# sequential_switch_rev_0_8.net
KiCad netlist of a schematic drawn in EAGLE
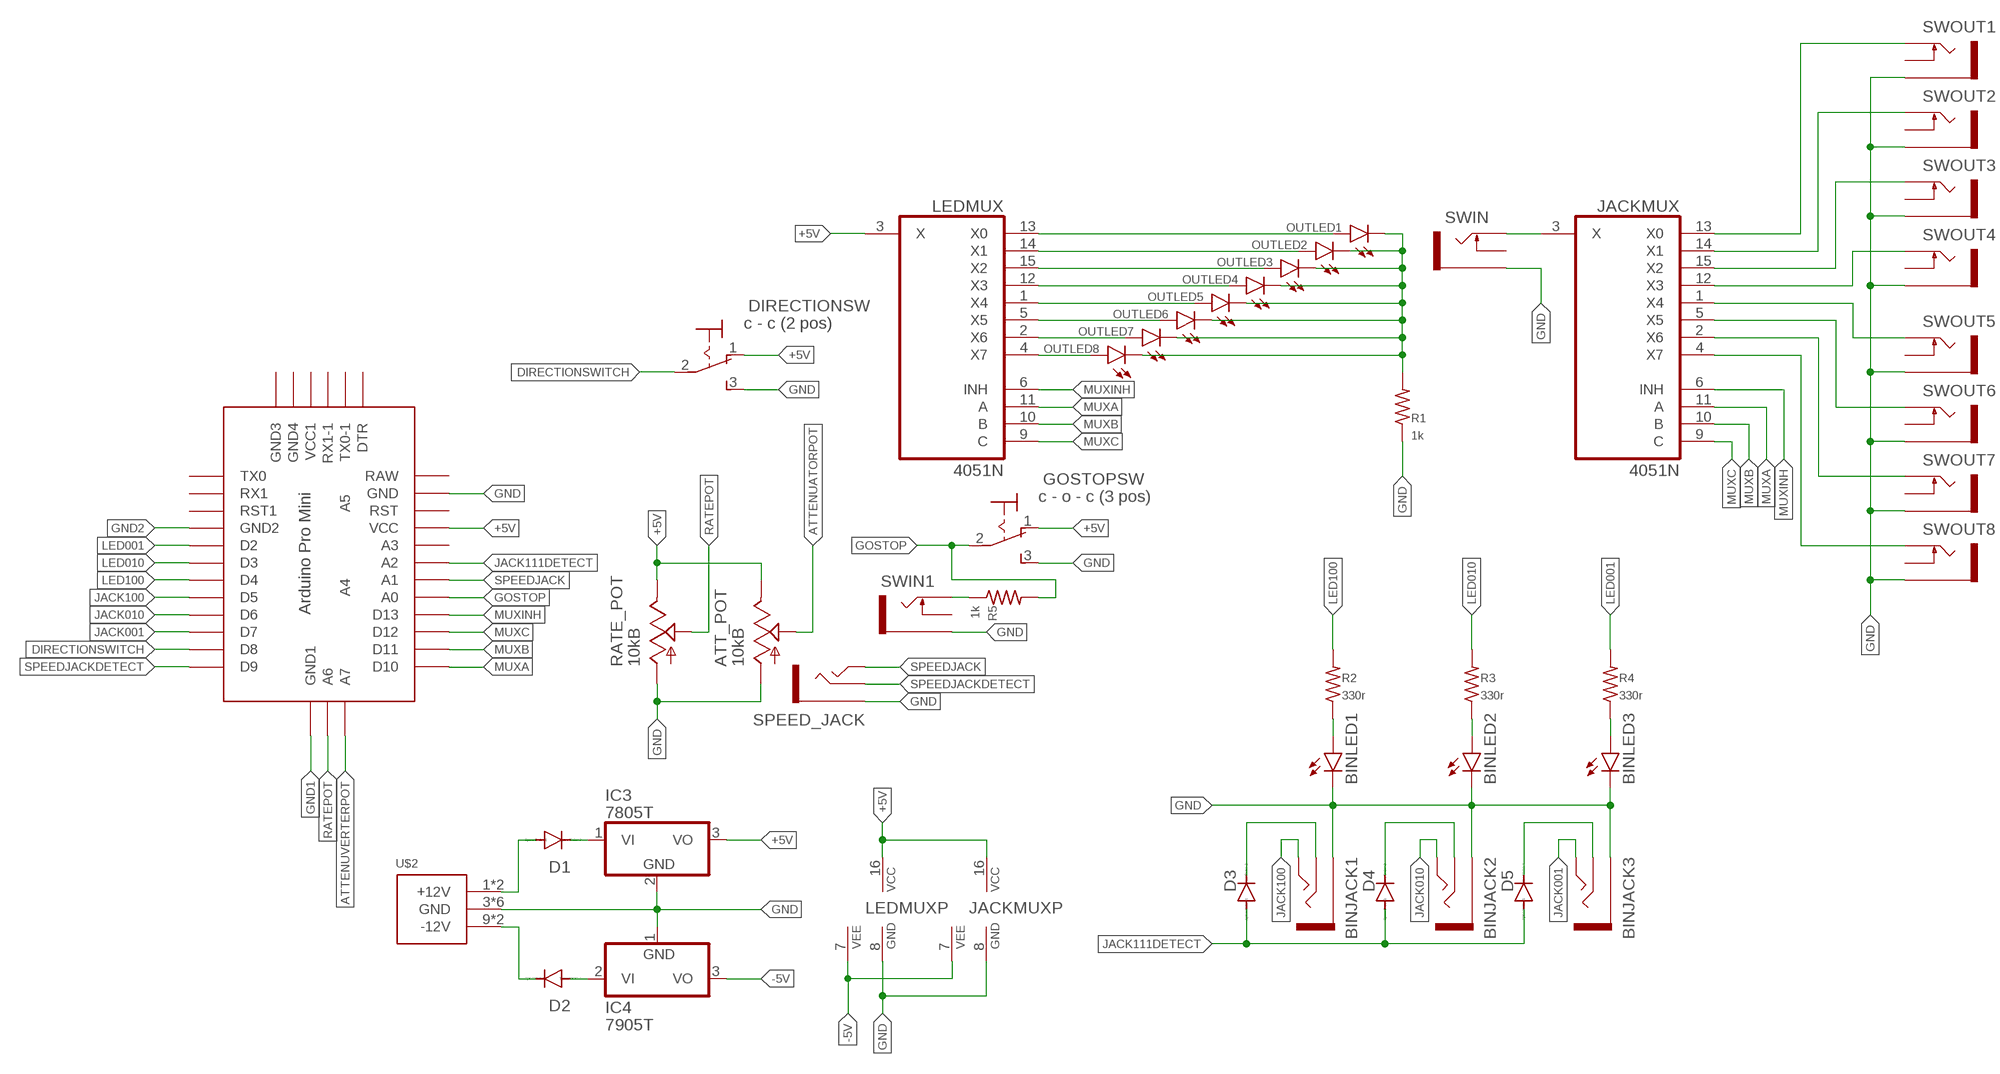
[diagram p0: schematic, sheet 1]

(export (version "E")
  (design (tool "Eeschema 10.0.6"))
  (components
    (comp (ref "ATT_POT")
      (value "10kB")
      (footprint "eagle-import:ALPS_POT_VERTICAL_PS")
      (libsource (lib "eagle-import") (part "POT_USVERTICAL_PS"))
    )
    (comp (ref "BINJACK1")
      (value "JACK-STEREO")
      (footprint "eagle-import:WQP-PJ301M-12_JACK")
      (libsource (lib "eagle-import") (part "JACK-STEREO"))
    )
    (comp (ref "BINJACK2")
      (value "JACK-STEREO")
      (footprint "eagle-import:WQP-PJ301M-12_JACK")
      (libsource (lib "eagle-import") (part "JACK-STEREO"))
    )
    (comp (ref "BINJACK3")
      (value "JACK-STEREO")
      (footprint "eagle-import:WQP-PJ301M-12_JACK")
      (libsource (lib "eagle-import") (part "JACK-STEREO"))
    )
    (comp (ref "BINLED1")
      (value "LED5MM")
      (footprint "eagle-import:LED5MM")
      (libsource (lib "eagle-import") (part "LED5MM"))
    )
    (comp (ref "BINLED2")
      (value "LED5MM")
      (footprint "eagle-import:LED5MM")
      (libsource (lib "eagle-import") (part "LED5MM"))
    )
    (comp (ref "BINLED3")
      (value "LED5MM")
      (footprint "eagle-import:LED5MM")
      (libsource (lib "eagle-import") (part "LED5MM"))
    )
    (comp (ref "D1")
      (value "1N4004")
      (footprint "eagle-import:DO41-10")
      (libsource (lib "eagle-import") (part "1N4004"))
    )
    (comp (ref "D2")
      (value "1N4004")
      (footprint "eagle-import:DO41-10")
      (libsource (lib "eagle-import") (part "1N4004"))
    )
    (comp (ref "D3")
      (value "1N4446")
      (footprint "eagle-import:DO35-10")
      (libsource (lib "eagle-import") (part "1N4446"))
    )
    (comp (ref "D4")
      (value "1N4446")
      (footprint "eagle-import:DO35-10")
      (libsource (lib "eagle-import") (part "1N4446"))
    )
    (comp (ref "D5")
      (value "1N4446")
      (footprint "eagle-import:DO35-10")
      (libsource (lib "eagle-import") (part "1N4446"))
    )
    (comp (ref "DIRECTIONSW")
      (value "c - c (2 pos)")
      (footprint "eagle-import:320-916")
      (libsource (lib "eagle-import") (part "320-916"))
    )
    (comp (ref "GOSTOPSW")
      (value "c - o - c (3 pos)")
      (footprint "eagle-import:320-916")
      (libsource (lib "eagle-import") (part "320-916"))
    )
    (comp (ref "IC3")
      (value "7805T")
      (footprint "eagle-import:TO220H")
      (libsource (lib "eagle-import") (part "78T05"))
    )
    (comp (ref "IC4")
      (value "7905T")
      (footprint "eagle-import:TO220H")
      (libsource (lib "eagle-import") (part "79T05"))
    )
    (comp (ref "JACKMUX")
      (value "4051N")
      (footprint "eagle-import:DIL16")
      (libsource (lib "eagle-import") (part "4051N"))
    )
    (comp (ref "LEDMUX")
      (value "4051N")
      (footprint "eagle-import:DIL16")
      (libsource (lib "eagle-import") (part "4051N"))
    )
    (comp (ref "OUTLED1")
      (value "LED3MM")
      (footprint "eagle-import:LED3MM")
      (libsource (lib "eagle-import") (part "LED3MM"))
    )
    (comp (ref "OUTLED2")
      (value "LED3MM")
      (footprint "eagle-import:LED3MM")
      (libsource (lib "eagle-import") (part "LED3MM"))
    )
    (comp (ref "OUTLED3")
      (value "LED3MM")
      (footprint "eagle-import:LED3MM")
      (libsource (lib "eagle-import") (part "LED3MM"))
    )
    (comp (ref "OUTLED4")
      (value "LED3MM")
      (footprint "eagle-import:LED3MM")
      (libsource (lib "eagle-import") (part "LED3MM"))
    )
    (comp (ref "OUTLED5")
      (value "LED3MM")
      (footprint "eagle-import:LED3MM")
      (libsource (lib "eagle-import") (part "LED3MM"))
    )
    (comp (ref "OUTLED6")
      (value "LED3MM")
      (footprint "eagle-import:LED3MM")
      (libsource (lib "eagle-import") (part "LED3MM"))
    )
    (comp (ref "OUTLED7")
      (value "LED3MM")
      (footprint "eagle-import:LED3MM")
      (libsource (lib "eagle-import") (part "LED3MM"))
    )
    (comp (ref "OUTLED8")
      (value "LED3MM")
      (footprint "eagle-import:LED3MM")
      (libsource (lib "eagle-import") (part "LED3MM"))
    )
    (comp (ref "R1")
      (value "1k")
      (footprint "eagle-import:0204_7")
      (libsource (lib "eagle-import") (part "R-US_0204/7"))
    )
    (comp (ref "R2")
      (value "330r")
      (footprint "eagle-import:0204_7")
      (libsource (lib "eagle-import") (part "R-US_0204/7"))
    )
    (comp (ref "R3")
      (value "330r")
      (footprint "eagle-import:0204_7")
      (libsource (lib "eagle-import") (part "R-US_0204/7"))
    )
    (comp (ref "R4")
      (value "330r")
      (footprint "eagle-import:0204_7")
      (libsource (lib "eagle-import") (part "R-US_0204/7"))
    )
    (comp (ref "R5")
      (value "1k")
      (footprint "eagle-import:0204_7")
      (libsource (lib "eagle-import") (part "R-US_0204/7"))
    )
    (comp (ref "RATE_POT")
      (value "10kB")
      (footprint "eagle-import:ALPS_POT_VERTICAL_PS")
      (libsource (lib "eagle-import") (part "POT_USVERTICAL_PS"))
    )
    (comp (ref "SPEED_JACK")
      (value "JACK-STEREO")
      (footprint "eagle-import:WQP-PJ301M-12_JACK")
      (libsource (lib "eagle-import") (part "JACK-STEREO"))
    )
    (comp (ref "SWIN")
      (value "WQP-PJ301M-12_JACK")
      (footprint "eagle-import:WQP-PJ301M-12_JACK")
      (libsource (lib "eagle-import") (part "WQP-PJ301M-12_JACK"))
    )
    (comp (ref "SWIN1")
      (value "WQP-PJ301M-12_JACK")
      (footprint "eagle-import:WQP-PJ301M-12_JACK")
      (libsource (lib "eagle-import") (part "WQP-PJ301M-12_JACK"))
    )
    (comp (ref "SWOUT1")
      (value "WQP-PJ301M-12_JACK")
      (footprint "eagle-import:WQP-PJ301M-12_JACK")
      (libsource (lib "eagle-import") (part "WQP-PJ301M-12_JACK"))
    )
    (comp (ref "SWOUT2")
      (value "WQP-PJ301M-12_JACK")
      (footprint "eagle-import:WQP-PJ301M-12_JACK")
      (libsource (lib "eagle-import") (part "WQP-PJ301M-12_JACK"))
    )
    (comp (ref "SWOUT3")
      (value "WQP-PJ301M-12_JACK")
      (footprint "eagle-import:WQP-PJ301M-12_JACK")
      (libsource (lib "eagle-import") (part "WQP-PJ301M-12_JACK"))
    )
    (comp (ref "SWOUT4")
      (value "WQP-PJ301M-12_JACK")
      (footprint "eagle-import:WQP-PJ301M-12_JACK")
      (libsource (lib "eagle-import") (part "WQP-PJ301M-12_JACK"))
    )
    (comp (ref "SWOUT5")
      (value "WQP-PJ301M-12_JACK")
      (footprint "eagle-import:WQP-PJ301M-12_JACK")
      (libsource (lib "eagle-import") (part "WQP-PJ301M-12_JACK"))
    )
    (comp (ref "SWOUT6")
      (value "WQP-PJ301M-12_JACK")
      (footprint "eagle-import:WQP-PJ301M-12_JACK")
      (libsource (lib "eagle-import") (part "WQP-PJ301M-12_JACK"))
    )
    (comp (ref "SWOUT7")
      (value "WQP-PJ301M-12_JACK")
      (footprint "eagle-import:WQP-PJ301M-12_JACK")
      (libsource (lib "eagle-import") (part "WQP-PJ301M-12_JACK"))
    )
    (comp (ref "SWOUT8")
      (value "WQP-PJ301M-12_JACK")
      (footprint "eagle-import:WQP-PJ301M-12_JACK")
      (libsource (lib "eagle-import") (part "WQP-PJ301M-12_JACK"))
    )
    (comp (ref "U$1")
      (value "ABK-PRO-MINI")
      (footprint "eagle-import:ABK-PRO-MINI")
      (libsource (lib "eagle-import") (part "ABK-PRO-MINI"))
    )
    (comp (ref "U$2")
      (value "POWER_SIMPLE")
      (footprint "eagle-import:POWER_10_NSTRIPE")
      (libsource (lib "eagle-import") (part "POWER_SIMPLE"))
    )
  )
  (nets
    (net (code "1") (name "+5V") (class "Default")
      (node (ref "ATT_POT") (pin "P$1") (pinfunction "E_P$1") (pintype "passive"))
      (node (ref "DIRECTIONSW") (pin "1") (pinfunction "O_1") (pintype "passive"))
      (node (ref "GOSTOPSW") (pin "1") (pinfunction "O_1") (pintype "passive"))
      (node (ref "IC3") (pin "3") (pinfunction "VO_3") (pintype "passive"))
      (node (ref "JACKMUX") (pin "16") (pinfunction "VCC_16") (pintype "power_in"))
      (node (ref "LEDMUX") (pin "16") (pinfunction "VCC_16") (pintype "power_in"))
      (node (ref "LEDMUX") (pin "3") (pinfunction "X_3") (pintype "bidirectional"))
      (node (ref "RATE_POT") (pin "P$1") (pinfunction "E_P$1") (pintype "passive"))
      (node (ref "U$1") (pin "VCC") (pinfunction "VCC_VCC") (pintype "bidirectional"))
    )
    (net (code "2") (name "-5V") (class "Default")
      (node (ref "IC4") (pin "3") (pinfunction "VO_3") (pintype "passive"))
      (node (ref "JACKMUX") (pin "7") (pinfunction "VEE_7") (pintype "power_in"))
      (node (ref "LEDMUX") (pin "7") (pinfunction "VEE_7") (pintype "power_in"))
    )
    (net (code "3") (name "ATTENUATORPOT") (class "Default")
      (node (ref "ATT_POT") (pin "P$2") (pinfunction "S_P$2") (pintype "passive"))
    )
    (net (code "4") (name "ATTENUVERTERPOT") (class "Default")
      (node (ref "U$1") (pin "A7") (pinfunction "A7_A7") (pintype "bidirectional"))
    )
    (net (code "5") (name "DIRECTIONSWITCH") (class "Default")
      (node (ref "DIRECTIONSW") (pin "2") (pinfunction "P_2") (pintype "passive"))
      (node (ref "U$1") (pin "D8") (pinfunction "D8_D8") (pintype "bidirectional"))
    )
    (net (code "6") (name "GND") (class "Default")
      (node (ref "ATT_POT") (pin "P$3") (pinfunction "A_P$3") (pintype "passive"))
      (node (ref "BINJACK1") (pin "RING") (pinfunction "RING_RING") (pintype "passive"))
      (node (ref "BINJACK2") (pin "RING") (pinfunction "RING_RING") (pintype "passive"))
      (node (ref "BINJACK3") (pin "RING") (pinfunction "RING_RING") (pintype "passive"))
      (node (ref "BINLED1") (pin "K") (pinfunction "C_K") (pintype "passive"))
      (node (ref "BINLED2") (pin "K") (pinfunction "C_K") (pintype "passive"))
      (node (ref "BINLED3") (pin "K") (pinfunction "C_K") (pintype "passive"))
      (node (ref "DIRECTIONSW") (pin "3") (pinfunction "S_3") (pintype "passive"))
      (node (ref "GOSTOPSW") (pin "3") (pinfunction "S_3") (pintype "passive"))
      (node (ref "IC3") (pin "2") (pinfunction "GND_2") (pintype "passive"))
      (node (ref "IC4") (pin "1") (pinfunction "GND_1") (pintype "passive"))
      (node (ref "JACKMUX") (pin "8") (pinfunction "GND_8") (pintype "power_in"))
      (node (ref "LEDMUX") (pin "8") (pinfunction "GND_8") (pintype "power_in"))
      (node (ref "R1") (pin "1") (pinfunction "1_1") (pintype "passive"))
      (node (ref "RATE_POT") (pin "P$3") (pinfunction "A_P$3") (pintype "passive"))
      (node (ref "SPEED_JACK") (pin "RING") (pinfunction "RING_RING") (pintype "passive"))
      (node (ref "SWIN") (pin "RING") (pinfunction "RING_RING") (pintype "passive"))
      (node (ref "SWIN1") (pin "RING") (pinfunction "RING_RING") (pintype "passive"))
      (node (ref "SWOUT1") (pin "RING") (pinfunction "RING_RING") (pintype "passive"))
      (node (ref "SWOUT2") (pin "RING") (pinfunction "RING_RING") (pintype "passive"))
      (node (ref "SWOUT3") (pin "RING") (pinfunction "RING_RING") (pintype "passive"))
      (node (ref "SWOUT4") (pin "RING") (pinfunction "RING_RING") (pintype "passive"))
      (node (ref "SWOUT5") (pin "RING") (pinfunction "RING_RING") (pintype "passive"))
      (node (ref "SWOUT6") (pin "RING") (pinfunction "RING_RING") (pintype "passive"))
      (node (ref "SWOUT7") (pin "RING") (pinfunction "RING_RING") (pintype "passive"))
      (node (ref "SWOUT8") (pin "RING") (pinfunction "RING_RING") (pintype "passive"))
      (node (ref "U$1") (pin "GND") (pinfunction "GND_GND") (pintype "bidirectional"))
      (node (ref "U$2") (pin "3") (pinfunction "GND_3") (pintype "bidirectional"))
      (node (ref "U$2") (pin "4") (pinfunction "GND_4") (pintype "bidirectional"))
      (node (ref "U$2") (pin "5") (pinfunction "GND_5") (pintype "bidirectional"))
      (node (ref "U$2") (pin "6") (pinfunction "GND_6") (pintype "bidirectional"))
      (node (ref "U$2") (pin "7") (pinfunction "GND_7") (pintype "bidirectional"))
      (node (ref "U$2") (pin "8") (pinfunction "GND_8") (pintype "bidirectional"))
    )
    (net (code "7") (name "GND1") (class "Default")
      (node (ref "U$1") (pin "GND4") (pinfunction "GND1_GND4") (pintype "bidirectional"))
    )
    (net (code "8") (name "GND2") (class "Default")
      (node (ref "U$1") (pin "GND1") (pinfunction "GND2_GND1") (pintype "bidirectional"))
    )
    (net (code "9") (name "GOSTOP") (class "Default")
      (node (ref "GOSTOPSW") (pin "2") (pinfunction "P_2") (pintype "passive"))
      (node (ref "R5") (pin "2") (pinfunction "2_2") (pintype "passive"))
      (node (ref "U$1") (pin "A0") (pinfunction "A0_A0") (pintype "bidirectional"))
    )
    (net (code "10") (name "JACK001") (class "Default")
      (node (ref "BINJACK3") (pin "TIP") (pinfunction "TIP_TIP") (pintype "passive"))
      (node (ref "U$1") (pin "D7") (pinfunction "D7_D7") (pintype "bidirectional"))
    )
    (net (code "11") (name "JACK010") (class "Default")
      (node (ref "BINJACK2") (pin "TIP") (pinfunction "TIP_TIP") (pintype "passive"))
      (node (ref "U$1") (pin "D6") (pinfunction "D6_D6") (pintype "bidirectional"))
    )
    (net (code "12") (name "JACK100") (class "Default")
      (node (ref "BINJACK1") (pin "TIP") (pinfunction "TIP_TIP") (pintype "passive"))
      (node (ref "U$1") (pin "D5") (pinfunction "D5_D5") (pintype "bidirectional"))
    )
    (net (code "13") (name "JACK111DETECT") (class "Default")
      (node (ref "D3") (pin "A") (pinfunction "A_A") (pintype "passive"))
      (node (ref "D4") (pin "A") (pinfunction "A_A") (pintype "passive"))
      (node (ref "D5") (pin "A") (pinfunction "A_A") (pintype "passive"))
      (node (ref "U$1") (pin "A2") (pinfunction "A2_A2") (pintype "bidirectional"))
    )
    (net (code "14") (name "LED001") (class "Default")
      (node (ref "R4") (pin "2") (pinfunction "2_2") (pintype "passive"))
      (node (ref "U$1") (pin "D2") (pinfunction "D2_D2") (pintype "bidirectional"))
    )
    (net (code "15") (name "LED010") (class "Default")
      (node (ref "R3") (pin "2") (pinfunction "2_2") (pintype "passive"))
      (node (ref "U$1") (pin "D3") (pinfunction "D3_D3") (pintype "bidirectional"))
    )
    (net (code "16") (name "LED100") (class "Default")
      (node (ref "R2") (pin "2") (pinfunction "2_2") (pintype "passive"))
      (node (ref "U$1") (pin "D4") (pinfunction "D4_D4") (pintype "bidirectional"))
    )
    (net (code "17") (name "MUXA") (class "Default")
      (node (ref "JACKMUX") (pin "11") (pinfunction "A_11") (pintype "input"))
      (node (ref "LEDMUX") (pin "11") (pinfunction "A_11") (pintype "input"))
      (node (ref "U$1") (pin "D10") (pinfunction "D10_D10") (pintype "bidirectional"))
    )
    (net (code "18") (name "MUXB") (class "Default")
      (node (ref "JACKMUX") (pin "10") (pinfunction "B_10") (pintype "input"))
      (node (ref "LEDMUX") (pin "10") (pinfunction "B_10") (pintype "input"))
      (node (ref "U$1") (pin "D11") (pinfunction "D11_D11") (pintype "bidirectional"))
    )
    (net (code "19") (name "MUXC") (class "Default")
      (node (ref "JACKMUX") (pin "9") (pinfunction "C_9") (pintype "input"))
      (node (ref "LEDMUX") (pin "9") (pinfunction "C_9") (pintype "input"))
      (node (ref "U$1") (pin "D12") (pinfunction "D12_D12") (pintype "bidirectional"))
    )
    (net (code "20") (name "MUXINH") (class "Default")
      (node (ref "JACKMUX") (pin "6") (pinfunction "INH_6") (pintype "input"))
      (node (ref "LEDMUX") (pin "6") (pinfunction "INH_6") (pintype "input"))
      (node (ref "U$1") (pin "D13") (pinfunction "D13_D13") (pintype "bidirectional"))
    )
    (net (code "21") (name "Net-(BINJACK1-PadSW)") (class "Default")
      (node (ref "BINJACK1") (pin "SW") (pinfunction "SW_SW") (pintype "passive"))
      (node (ref "D3") (pin "C") (pinfunction "C_C") (pintype "passive"))
    )
    (net (code "22") (name "Net-(BINJACK2-PadSW)") (class "Default")
      (node (ref "BINJACK2") (pin "SW") (pinfunction "SW_SW") (pintype "passive"))
      (node (ref "D4") (pin "C") (pinfunction "C_C") (pintype "passive"))
    )
    (net (code "23") (name "Net-(BINJACK3-PadSW)") (class "Default")
      (node (ref "BINJACK3") (pin "SW") (pinfunction "SW_SW") (pintype "passive"))
      (node (ref "D5") (pin "C") (pinfunction "C_C") (pintype "passive"))
    )
    (net (code "24") (name "Net-(BINLED1-PadA)") (class "Default")
      (node (ref "BINLED1") (pin "A") (pinfunction "A_A") (pintype "passive"))
      (node (ref "R2") (pin "1") (pinfunction "1_1") (pintype "passive"))
    )
    (net (code "25") (name "Net-(BINLED2-PadA)") (class "Default")
      (node (ref "BINLED2") (pin "A") (pinfunction "A_A") (pintype "passive"))
      (node (ref "R3") (pin "1") (pinfunction "1_1") (pintype "passive"))
    )
    (net (code "26") (name "Net-(BINLED3-PadA)") (class "Default")
      (node (ref "BINLED3") (pin "A") (pinfunction "A_A") (pintype "passive"))
      (node (ref "R4") (pin "1") (pinfunction "1_1") (pintype "passive"))
    )
    (net (code "27") (name "Net-(D1-PadA)") (class "Default")
      (node (ref "D1") (pin "A") (pinfunction "A_A") (pintype "passive"))
      (node (ref "U$2") (pin "1") (pinfunction "+12V_1") (pintype "bidirectional"))
      (node (ref "U$2") (pin "2") (pinfunction "+12V_2") (pintype "bidirectional"))
    )
    (net (code "28") (name "Net-(D2-PadC)") (class "Default")
      (node (ref "D2") (pin "C") (pinfunction "C_C") (pintype "passive"))
      (node (ref "U$2") (pin "10") (pinfunction "-12V_10") (pintype "bidirectional"))
      (node (ref "U$2") (pin "9") (pinfunction "-12V_9") (pintype "bidirectional"))
    )
    (net (code "29") (name "Net-(IC3-VI)") (class "Default")
      (node (ref "D1") (pin "C") (pinfunction "C_C") (pintype "passive"))
      (node (ref "IC3") (pin "1") (pinfunction "VI_1") (pintype "input"))
    )
    (net (code "30") (name "Net-(IC4-VI)") (class "Default")
      (node (ref "D2") (pin "A") (pinfunction "A_A") (pintype "passive"))
      (node (ref "IC4") (pin "2") (pinfunction "VI_2") (pintype "input"))
    )
    (net (code "31") (name "Net-(JACKMUXA-X)") (class "Default")
      (node (ref "JACKMUX") (pin "3") (pinfunction "X_3") (pintype "bidirectional"))
      (node (ref "SWIN") (pin "TIP") (pinfunction "TIP_TIP") (pintype "passive"))
    )
    (net (code "32") (name "Net-(JACKMUXA-X0)") (class "Default")
      (node (ref "JACKMUX") (pin "13") (pinfunction "X0_13") (pintype "bidirectional"))
      (node (ref "SWOUT1") (pin "TIP") (pinfunction "TIP_TIP") (pintype "passive"))
    )
    (net (code "33") (name "Net-(JACKMUXA-X1)") (class "Default")
      (node (ref "JACKMUX") (pin "14") (pinfunction "X1_14") (pintype "bidirectional"))
      (node (ref "SWOUT2") (pin "TIP") (pinfunction "TIP_TIP") (pintype "passive"))
    )
    (net (code "34") (name "Net-(JACKMUXA-X2)") (class "Default")
      (node (ref "JACKMUX") (pin "15") (pinfunction "X2_15") (pintype "bidirectional"))
      (node (ref "SWOUT3") (pin "TIP") (pinfunction "TIP_TIP") (pintype "passive"))
    )
    (net (code "35") (name "Net-(JACKMUXA-X3)") (class "Default")
      (node (ref "JACKMUX") (pin "12") (pinfunction "X3_12") (pintype "bidirectional"))
      (node (ref "SWOUT4") (pin "TIP") (pinfunction "TIP_TIP") (pintype "passive"))
    )
    (net (code "36") (name "Net-(JACKMUXA-X4)") (class "Default")
      (node (ref "JACKMUX") (pin "1") (pinfunction "X4_1") (pintype "bidirectional"))
      (node (ref "SWOUT5") (pin "TIP") (pinfunction "TIP_TIP") (pintype "passive"))
    )
    (net (code "37") (name "Net-(JACKMUXA-X5)") (class "Default")
      (node (ref "JACKMUX") (pin "5") (pinfunction "X5_5") (pintype "bidirectional"))
      (node (ref "SWOUT6") (pin "TIP") (pinfunction "TIP_TIP") (pintype "passive"))
    )
    (net (code "38") (name "Net-(JACKMUXA-X6)") (class "Default")
      (node (ref "JACKMUX") (pin "2") (pinfunction "X6_2") (pintype "bidirectional"))
      (node (ref "SWOUT7") (pin "TIP") (pinfunction "TIP_TIP") (pintype "passive"))
    )
    (net (code "39") (name "Net-(JACKMUXA-X7)") (class "Default")
      (node (ref "JACKMUX") (pin "4") (pinfunction "X7_4") (pintype "bidirectional"))
      (node (ref "SWOUT8") (pin "TIP") (pinfunction "TIP_TIP") (pintype "passive"))
    )
    (net (code "40") (name "Net-(LEDMUXA-X0)") (class "Default")
      (node (ref "LEDMUX") (pin "13") (pinfunction "X0_13") (pintype "bidirectional"))
      (node (ref "OUTLED1") (pin "A") (pinfunction "A_A") (pintype "passive"))
    )
    (net (code "41") (name "Net-(LEDMUXA-X1)") (class "Default")
      (node (ref "LEDMUX") (pin "14") (pinfunction "X1_14") (pintype "bidirectional"))
      (node (ref "OUTLED2") (pin "A") (pinfunction "A_A") (pintype "passive"))
    )
    (net (code "42") (name "Net-(LEDMUXA-X2)") (class "Default")
      (node (ref "LEDMUX") (pin "15") (pinfunction "X2_15") (pintype "bidirectional"))
      (node (ref "OUTLED3") (pin "A") (pinfunction "A_A") (pintype "passive"))
    )
    (net (code "43") (name "Net-(LEDMUXA-X3)") (class "Default")
      (node (ref "LEDMUX") (pin "12") (pinfunction "X3_12") (pintype "bidirectional"))
      (node (ref "OUTLED4") (pin "A") (pinfunction "A_A") (pintype "passive"))
    )
    (net (code "44") (name "Net-(LEDMUXA-X4)") (class "Default")
      (node (ref "LEDMUX") (pin "1") (pinfunction "X4_1") (pintype "bidirectional"))
      (node (ref "OUTLED5") (pin "A") (pinfunction "A_A") (pintype "passive"))
    )
    (net (code "45") (name "Net-(LEDMUXA-X5)") (class "Default")
      (node (ref "LEDMUX") (pin "5") (pinfunction "X5_5") (pintype "bidirectional"))
      (node (ref "OUTLED6") (pin "A") (pinfunction "A_A") (pintype "passive"))
    )
    (net (code "46") (name "Net-(LEDMUXA-X6)") (class "Default")
      (node (ref "LEDMUX") (pin "2") (pinfunction "X6_2") (pintype "bidirectional"))
      (node (ref "OUTLED7") (pin "A") (pinfunction "A_A") (pintype "passive"))
    )
    (net (code "47") (name "Net-(LEDMUXA-X7)") (class "Default")
      (node (ref "LEDMUX") (pin "4") (pinfunction "X7_4") (pintype "bidirectional"))
      (node (ref "OUTLED8") (pin "A") (pinfunction "A_A") (pintype "passive"))
    )
    (net (code "48") (name "Net-(OUTLED1-C)") (class "Default")
      (node (ref "OUTLED1") (pin "K") (pinfunction "C_K") (pintype "passive"))
      (node (ref "OUTLED2") (pin "K") (pinfunction "C_K") (pintype "passive"))
      (node (ref "OUTLED3") (pin "K") (pinfunction "C_K") (pintype "passive"))
      (node (ref "OUTLED4") (pin "K") (pinfunction "C_K") (pintype "passive"))
      (node (ref "OUTLED5") (pin "K") (pinfunction "C_K") (pintype "passive"))
      (node (ref "OUTLED6") (pin "K") (pinfunction "C_K") (pintype "passive"))
      (node (ref "OUTLED7") (pin "K") (pinfunction "C_K") (pintype "passive"))
      (node (ref "OUTLED8") (pin "K") (pinfunction "C_K") (pintype "passive"))
      (node (ref "R1") (pin "2") (pinfunction "2_2") (pintype "passive"))
    )
    (net (code "49") (name "Net-(R5-Pad1)") (class "Default")
      (node (ref "R5") (pin "1") (pinfunction "1_1") (pintype "passive"))
      (node (ref "SWIN1") (pin "TIP") (pinfunction "TIP_TIP") (pintype "passive"))
    )
    (net (code "50") (name "RATEPOT") (class "Default")
      (node (ref "RATE_POT") (pin "P$2") (pinfunction "S_P$2") (pintype "passive"))
      (node (ref "U$1") (pin "A6") (pinfunction "A6_A6") (pintype "bidirectional"))
    )
    (net (code "51") (name "SPEEDJACK") (class "Default")
      (node (ref "SPEED_JACK") (pin "TIP") (pinfunction "TIP_TIP") (pintype "passive"))
      (node (ref "U$1") (pin "A1") (pinfunction "A1_A1") (pintype "bidirectional"))
    )
    (net (code "52") (name "SPEEDJACKDETECT") (class "Default")
      (node (ref "SPEED_JACK") (pin "SW") (pinfunction "SW_SW") (pintype "passive"))
      (node (ref "U$1") (pin "D9") (pinfunction "D9_D9") (pintype "bidirectional"))
    )
    (net (code "53") (name "unconnected-(SWIN-PadSW)") (class "Default")
      (node (ref "SWIN") (pin "SW") (pinfunction "SW_SW") (pintype "passive"))
    )
    (net (code "54") (name "unconnected-(SWIN1-PadSW)") (class "Default")
      (node (ref "SWIN1") (pin "SW") (pinfunction "SW_SW") (pintype "passive"))
    )
    (net (code "55") (name "unconnected-(SWOUT1-PadSW)") (class "Default")
      (node (ref "SWOUT1") (pin "SW") (pinfunction "SW_SW") (pintype "passive"))
    )
    (net (code "56") (name "unconnected-(SWOUT2-PadSW)") (class "Default")
      (node (ref "SWOUT2") (pin "SW") (pinfunction "SW_SW") (pintype "passive"))
    )
    (net (code "57") (name "unconnected-(SWOUT3-PadSW)") (class "Default")
      (node (ref "SWOUT3") (pin "SW") (pinfunction "SW_SW") (pintype "passive"))
    )
    (net (code "58") (name "unconnected-(SWOUT4-PadSW)") (class "Default")
      (node (ref "SWOUT4") (pin "SW") (pinfunction "SW_SW") (pintype "passive"))
    )
    (net (code "59") (name "unconnected-(SWOUT5-PadSW)") (class "Default")
      (node (ref "SWOUT5") (pin "SW") (pinfunction "SW_SW") (pintype "passive"))
    )
    (net (code "60") (name "unconnected-(SWOUT6-PadSW)") (class "Default")
      (node (ref "SWOUT6") (pin "SW") (pinfunction "SW_SW") (pintype "passive"))
    )
    (net (code "61") (name "unconnected-(SWOUT7-PadSW)") (class "Default")
      (node (ref "SWOUT7") (pin "SW") (pinfunction "SW_SW") (pintype "passive"))
    )
    (net (code "62") (name "unconnected-(SWOUT8-PadSW)") (class "Default")
      (node (ref "SWOUT8") (pin "SW") (pinfunction "SW_SW") (pintype "passive"))
    )
    (net (code "63") (name "unconnected-(U$1-GND3-PadGND2)") (class "Default")
      (node (ref "U$1") (pin "GND2") (pinfunction "GND3_GND2") (pintype "bidirectional"))
    )
    (net (code "64") (name "unconnected-(U$1-GND4-PadGND3)") (class "Default")
      (node (ref "U$1") (pin "GND3") (pinfunction "GND4_GND3") (pintype "bidirectional"))
    )
    (net (code "65") (name "unconnected-(U$1-PadA3)") (class "Default")
      (node (ref "U$1") (pin "A3") (pinfunction "A3_A3") (pintype "bidirectional"))
    )
    (net (code "66") (name "unconnected-(U$1-PadA4)") (class "Default")
      (node (ref "U$1") (pin "A4") (pinfunction "A4_A4") (pintype "bidirectional"))
    )
    (net (code "67") (name "unconnected-(U$1-PadA5)") (class "Default")
      (node (ref "U$1") (pin "A5") (pinfunction "A5_A5") (pintype "bidirectional"))
    )
    (net (code "68") (name "unconnected-(U$1-PadDTR)") (class "Default")
      (node (ref "U$1") (pin "DTR") (pinfunction "DTR_DTR") (pintype "bidirectional"))
    )
    (net (code "69") (name "unconnected-(U$1-PadRAW)") (class "Default")
      (node (ref "U$1") (pin "RAW") (pinfunction "RAW_RAW") (pintype "bidirectional"))
    )
    (net (code "70") (name "unconnected-(U$1-PadRST)") (class "Default")
      (node (ref "U$1") (pin "RST") (pinfunction "RST_RST") (pintype "bidirectional"))
    )
    (net (code "71") (name "unconnected-(U$1-PadRST1)") (class "Default")
      (node (ref "U$1") (pin "RST1") (pinfunction "RST1_RST1") (pintype "bidirectional"))
    )
    (net (code "72") (name "unconnected-(U$1-PadRX1)") (class "Default")
      (node (ref "U$1") (pin "RX1") (pinfunction "RX1_RX1") (pintype "bidirectional"))
    )
    (net (code "73") (name "unconnected-(U$1-PadRX1-1)") (class "Default")
      (node (ref "U$1") (pin "RX1-1") (pinfunction "RX1-1_RX1-1") (pintype "bidirectional"))
    )
    (net (code "74") (name "unconnected-(U$1-PadTX0)") (class "Default")
      (node (ref "U$1") (pin "TX0") (pinfunction "TX0_TX0") (pintype "bidirectional"))
    )
    (net (code "75") (name "unconnected-(U$1-PadTX0-1)") (class "Default")
      (node (ref "U$1") (pin "TX0-1") (pinfunction "TX0-1_TX0-1") (pintype "bidirectional"))
    )
    (net (code "76") (name "unconnected-(U$1-PadVCC1)") (class "Default")
      (node (ref "U$1") (pin "VCC1") (pinfunction "VCC1_VCC1") (pintype "bidirectional"))
    )
  )
)
